# Controlador_de_corriente.net
KiCad netlist of a schematic drawn in Altium Designer
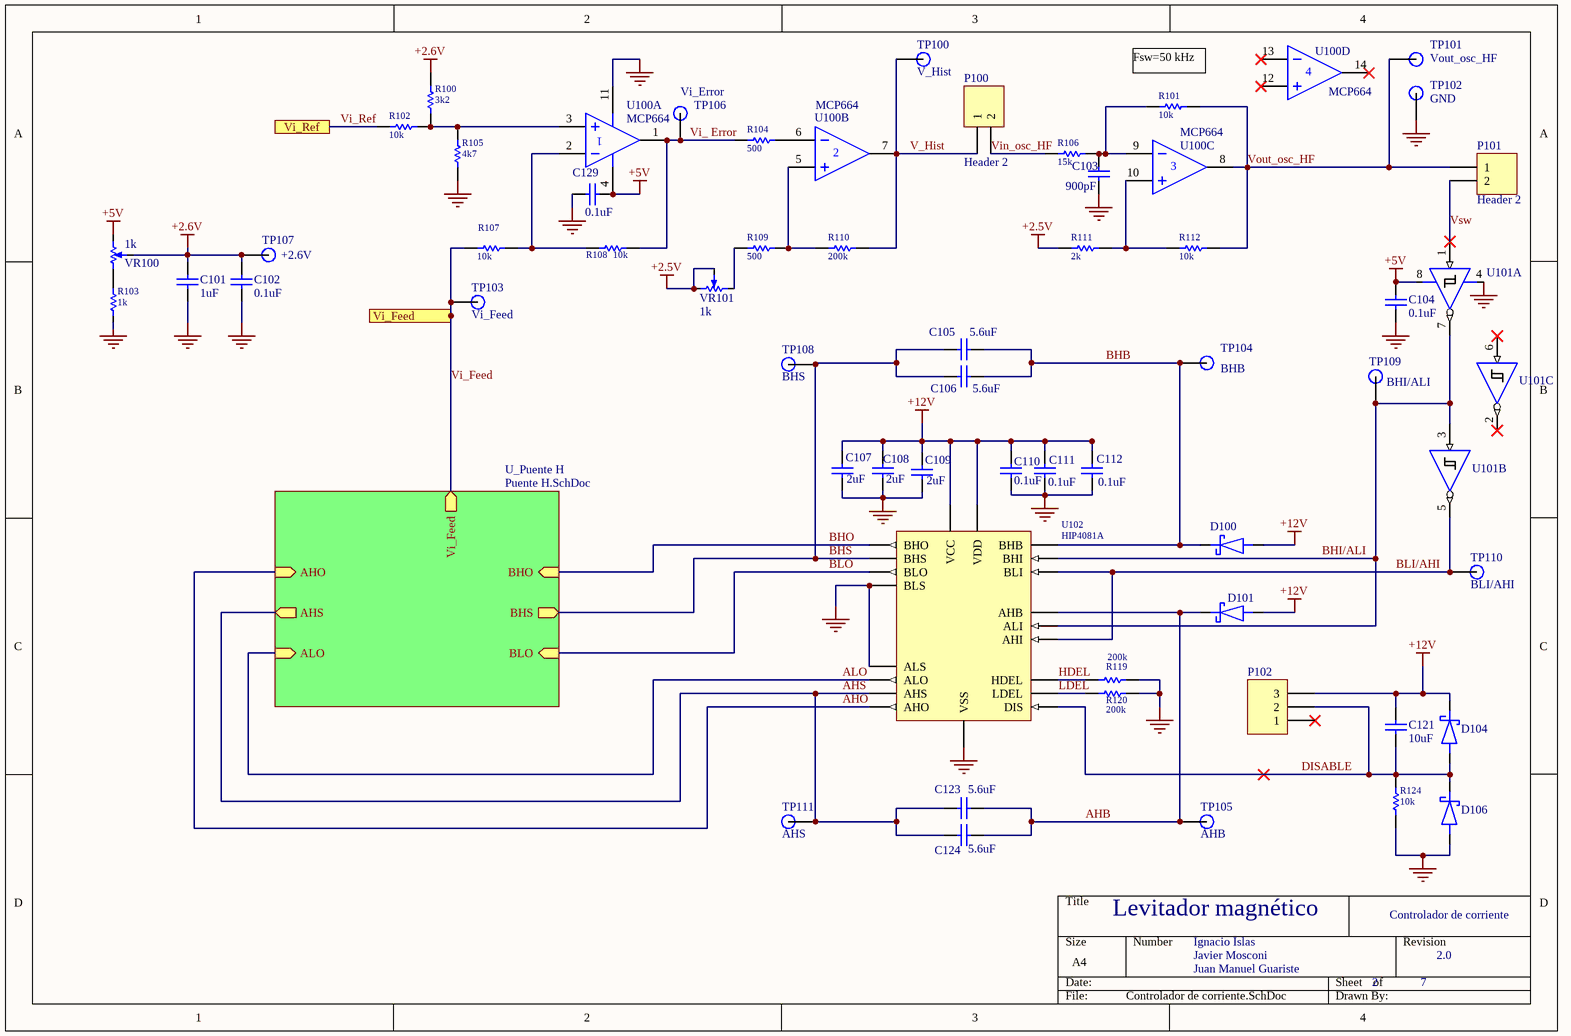
[diagram p0: Controlador de corriente.SchDoc]

(export (version "E")
  (design (tool "Eeschema 10.0.6"))
  (components
    (comp (ref "C101")
      (value "1uF")
      (footprint "C1206")
      (description "CAP CER 1UF 25V X7R 1206")
      (fields (field (name "MANUFACTURER") "CAL-CHIP ELECTRONICS, INC.") (field (name "Comment") "Capacitor"))
      (libsource (lib "Levitador_GMI") (part "Capacitor"))
    )
    (comp (ref "C102")
      (value "0.1uF")
      (footprint "C1206")
      (description "CAP CER 0.1UF 50V X7R 1206")
      (fields (field (name "MANUFACTURER") "Venkel") (field (name "Comment") "Capacitor"))
      (libsource (lib "Levitador_GMI") (part "Capacitor"))
    )
    (comp (ref "C103")
      (value "900pF")
      (footprint "C1206")
      (description "CAP CER 910PF 50V NP0 1206")
      (fields (field (name "MANUFACTURER") "KEMET") (field (name "Comment") "Capacitor"))
      (libsource (lib "Levitador_GMI") (part "Capacitor"))
    )
    (comp (ref "C104")
      (value "0.1uF")
      (footprint "C1206")
      (description "CAP CER 0.1UF 50V X7R 1206")
      (fields (field (name "MANUFACTURER") "Venkel") (field (name "Comment") "Capacitor"))
      (libsource (lib "Levitador_GMI") (part "Capacitor"))
    )
    (comp (ref "C105")
      (value "5.6uF")
      (footprint "C1206")
      (description "CAP CER 4.7UF 50V X7R 1206")
      (fields (field (name "MANUFACTURER") "Samsung Electro-Mechanics") (field (name "Comment") "Capacitor"))
      (libsource (lib "Levitador_GMI") (part "Capacitor"))
    )
    (comp (ref "C106")
      (value "5.6uF")
      (footprint "C1206")
      (description "CAP CER 4.7UF 50V X7R 1206")
      (fields (field (name "MANUFACTURER") "Samsung Electro-Mechanics") (field (name "Comment") "Capacitor"))
      (libsource (lib "Levitador_GMI") (part "Capacitor"))
    )
    (comp (ref "C107")
      (value "2uF")
      (footprint "C1206")
      (description "CAP1206 X5R 2.2UF 20% 35V")
      (fields (field (name "MANUFACTURER") "CAL-CHIP ELECTRONICS, INC.") (field (name "Comment") "Capacitor"))
      (libsource (lib "Levitador_GMI") (part "Capacitor"))
    )
    (comp (ref "C108")
      (value "2uF")
      (footprint "C1206")
      (description "CAP1206 X5R 2.2UF 20% 35V")
      (fields (field (name "MANUFACTURER") "CAL-CHIP ELECTRONICS, INC.") (field (name "Comment") "Capacitor"))
      (libsource (lib "Levitador_GMI") (part "Capacitor"))
    )
    (comp (ref "C109")
      (value "2uF")
      (footprint "C1206")
      (description "CAP1206 X5R 2.2UF 20% 35V")
      (fields (field (name "MANUFACTURER") "CAL-CHIP ELECTRONICS, INC.") (field (name "Comment") "Capacitor"))
      (libsource (lib "Levitador_GMI") (part "Capacitor"))
    )
    (comp (ref "C110")
      (value "0.1uF")
      (footprint "C1206")
      (description "CAP CER 0.1UF 50V X7R 1206")
      (fields (field (name "MANUFACTURER") "Venkel") (field (name "Comment") "Capacitor"))
      (libsource (lib "Levitador_GMI") (part "Capacitor"))
    )
    (comp (ref "C111")
      (value "0.1uF")
      (footprint "C1206")
      (description "CAP CER 0.1UF 50V X7R 1206")
      (fields (field (name "MANUFACTURER") "Venkel") (field (name "Comment") "Capacitor"))
      (libsource (lib "Levitador_GMI") (part "Capacitor"))
    )
    (comp (ref "C112")
      (value "0.1uF")
      (footprint "C1206")
      (description "CAP CER 0.1UF 50V X7R 1206")
      (fields (field (name "MANUFACTURER") "Venkel") (field (name "Comment") "Capacitor"))
      (libsource (lib "Levitador_GMI") (part "Capacitor"))
    )
    (comp (ref "C121")
      (value "10uF")
      (footprint "C1206")
      (description "CAP CER 10UF 16V X7R 1206")
      (fields (field (name "MANUFACTURER") "CAL-CHIP ELECTRONICS, INC.") (field (name "Comment") "Capacitor"))
      (libsource (lib "Levitador_GMI") (part "Capacitor"))
    )
    (comp (ref "C123")
      (value "5.6uF")
      (footprint "C1206")
      (description "CAP CER 4.7UF 50V X7R 1206")
      (fields (field (name "MANUFACTURER") "Samsung Electro-Mechanics") (field (name "Comment") "Capacitor"))
      (libsource (lib "Levitador_GMI") (part "Capacitor"))
    )
    (comp (ref "C124")
      (value "5.6uF")
      (footprint "C1206")
      (description "CAP CER 4.7UF 50V X7R 1206")
      (fields (field (name "MANUFACTURER") "Samsung Electro-Mechanics") (field (name "Comment") "Capacitor"))
      (libsource (lib "Levitador_GMI") (part "Capacitor"))
    )
    (comp (ref "C129")
      (value "0.1uF")
      (footprint "C1206")
      (description "CAP CER 0.1UF 50V X7R 1206")
      (fields (field (name "MANUFACTURER") "Venkel") (field (name "Comment") "Capacitor"))
      (libsource (lib "Levitador_GMI") (part "Capacitor"))
    )
    (comp (ref "D100")
      (value "RSX205LAM30TR")
      (footprint "SODFL4725X105N")
      (description "DIODE SCHOTTKY 30V 2A PMDTM")
      (libsource (lib "Levitador_GMI") (part "RSX205LAM30TR"))
    )
    (comp (ref "D101")
      (value "RSX205LAM30TR")
      (footprint "SODFL4725X105N")
      (description "DIODE SCHOTTKY 30V 2A PMDTM")
      (libsource (lib "Levitador_GMI") (part "RSX205LAM30TR"))
    )
    (comp (ref "D104")
      (value "RSX205LAM30TR")
      (footprint "SODFL4725X105N")
      (description "DIODE SCHOTTKY 30V 2A PMDTM")
      (libsource (lib "Levitador_GMI") (part "RSX205LAM30TR"))
    )
    (comp (ref "D106")
      (value "RSX205LAM30TR")
      (footprint "SODFL4725X105N")
      (description "DIODE SCHOTTKY 30V 2A PMDTM")
      (libsource (lib "Levitador_GMI") (part "RSX205LAM30TR"))
    )
    (comp (ref "P100")
      (value "Header 2")
      (footprint "HDR1X2")
      (description "TERM BLK 2P SIDE ENT 2.54MM PCB")
      (fields (field (name "MANUFACTURER") "TE Connectivity AMP Connectors"))
      (libsource (lib "Levitador_GMI") (part "Header 2"))
    )
    (comp (ref "P101")
      (value "Header 2")
      (footprint "HDR1X2")
      (description "TERM BLK 2P SIDE ENT 2.54MM PCB")
      (fields (field (name "MANUFACTURER") "TE Connectivity AMP Connectors"))
      (libsource (lib "") (part "Header 2_1"))
    )
    (comp (ref "P102")
      (value "Header 3")
      (footprint "HDR1X3")
      (description "TERM BLK 3P SIDE ENT 2.54MM PCB")
      (fields (field (name "MANUFACTURER") "TE Connectivity AMP Connectors"))
      (libsource (lib "Levitador_GMI") (part "Header 3"))
    )
    (comp (ref "R100")
      (value "3k2")
      (footprint "Levitador_GMI:R1206")
      (description "RES 3.2K OHM 1% 1/4W 1206")
      (fields (field (name "MANUFACTURER") "KOA Speer Electronics, Inc.") (field (name "TOLERANCE") "1%"))
      (libsource (lib "Levitador_GMI") (part "R1206"))
    )
    (comp (ref "R101")
      (value "10k")
      (footprint "Levitador_GMI:R1206")
      (description "RES 10K OHM 1% 1/4W 1206")
      (fields (field (name "MANUFACTURER") "YAGEO") (field (name "TOLERANCE") "1%"))
      (libsource (lib "Levitador_GMI") (part "R1206"))
    )
    (comp (ref "R102")
      (value "10k")
      (footprint "Levitador_GMI:R1206")
      (description "RES 10K OHM 1% 1/4W 1206")
      (fields (field (name "MANUFACTURER") "YAGEO") (field (name "TOLERANCE") "1%"))
      (libsource (lib "Levitador_GMI") (part "R1206"))
    )
    (comp (ref "R103")
      (value "1k")
      (footprint "Levitador_GMI:R1206")
      (description "RES 1K OHM 1% 1/4W 1206")
      (fields (field (name "MANUFACTURER") "Stackpole Electronics Inc") (field (name "TOLERANCE") "1%"))
      (libsource (lib "Levitador_GMI") (part "R1206"))
    )
    (comp (ref "R104")
      (value "500")
      (footprint "Levitador_GMI:R1206")
      (description "RES SMD 500 OHM 0.1% 0.3W 1206")
      (fields
        (field (name "MANUFACTURER") "Vishay Foil Resistors (Division of Vishay Precision Group)")
        (field (name "TOLERANCE") "0.1%")
      )
      (libsource (lib "Levitador_GMI") (part "R1206"))
    )
    (comp (ref "R105")
      (value "4k7")
      (footprint "Levitador_GMI:R1206")
      (description "RES 4.7K OHM 1% 1/4W 1206")
      (fields (field (name "MANUFACTURER") "Stackpole Electronics Inc") (field (name "TOLERANCE") "1%"))
      (libsource (lib "Levitador_GMI") (part "R1206"))
    )
    (comp (ref "R106")
      (value "15k")
      (footprint "Levitador_GMI:R1206")
      (description "RES 15K OHM 1% 1/4W 1206")
      (fields (field (name "MANUFACTURER") "Vishay Dale") (field (name "TOLERANCE") "1%"))
      (libsource (lib "Levitador_GMI") (part "R1206"))
    )
    (comp (ref "R107")
      (value "10k")
      (footprint "Levitador_GMI:R1206")
      (description "RES 10K OHM 1% 1/4W 1206")
      (fields (field (name "MANUFACTURER") "YAGEO") (field (name "TOLERANCE") "1%"))
      (libsource (lib "Levitador_GMI") (part "R1206"))
    )
    (comp (ref "R108")
      (value "10k")
      (footprint "Levitador_GMI:R1206")
      (description "RES 10K OHM 1% 1/4W 1206")
      (fields (field (name "MANUFACTURER") "YAGEO") (field (name "TOLERANCE") "1%"))
      (libsource (lib "Levitador_GMI") (part "R1206"))
    )
    (comp (ref "R109")
      (value "500")
      (footprint "Levitador_GMI:R1206")
      (description "RES SMD 500 OHM 0.1% 0.3W 1206")
      (fields
        (field (name "MANUFACTURER") "Vishay Foil Resistors (Division of Vishay Precision Group)")
        (field (name "TOLERANCE") "0.1%")
      )
      (libsource (lib "Levitador_GMI") (part "R1206"))
    )
    (comp (ref "R110")
      (value "200k")
      (footprint "Levitador_GMI:R1206")
      (description "RES 200K OHM 1% 1/4W 1206")
      (fields (field (name "MANUFACTURER") "YAGEO") (field (name "TOLERANCE") "1%"))
      (libsource (lib "Levitador_GMI") (part "R1206"))
    )
    (comp (ref "R111")
      (value "2k")
      (footprint "Levitador_GMI:R1206")
      (description "RES 2K OHM 1% 1/4W 1206")
      (fields (field (name "MANUFACTURER") "Stackpole Electronics Inc") (field (name "TOLERANCE") "1%"))
      (libsource (lib "Levitador_GMI") (part "R1206"))
    )
    (comp (ref "R112")
      (value "10k")
      (footprint "Levitador_GMI:R1206")
      (description "RES 10K OHM 1% 1/4W 1206")
      (fields (field (name "MANUFACTURER") "YAGEO") (field (name "TOLERANCE") "1%"))
      (libsource (lib "Levitador_GMI") (part "R1206"))
    )
    (comp (ref "R119")
      (value "200k")
      (footprint "Levitador_GMI:R1206")
      (description "RES 200K OHM 1% 1/4W 1206")
      (fields (field (name "MANUFACTURER") "YAGEO") (field (name "TOLERANCE") "1%"))
      (libsource (lib "Levitador_GMI") (part "R1206"))
    )
    (comp (ref "R120")
      (value "200k")
      (footprint "Levitador_GMI:R1206")
      (description "RES 200K OHM 1% 1/4W 1206")
      (fields (field (name "MANUFACTURER") "YAGEO") (field (name "TOLERANCE") "1%"))
      (libsource (lib "Levitador_GMI") (part "R1206"))
    )
    (comp (ref "R124")
      (value "10k")
      (footprint "Levitador_GMI:R1206")
      (description "RES 10K OHM 1% 1/4W 1206")
      (fields (field (name "MANUFACTURER") "YAGEO") (field (name "TOLERANCE") "1%"))
      (libsource (lib "Levitador_GMI") (part "R1206"))
    )
    (comp (ref "TP100")
      (value "V_Hist")
      (footprint "TestPoint Keystone 5000 Silver-Red")
      (description "PC TEST POINT MINIATURE RED")
      (fields (field (name "MANUFACTURER") "Keystone Electronics"))
      (libsource (lib "Levitador_GMI") (part "Testpoint"))
    )
    (comp (ref "TP101")
      (value "Vout_osc_HF")
      (footprint "TestPoint Keystone 5000 Silver-Red")
      (description "PC TEST POINT MINIATURE RED")
      (fields (field (name "MANUFACTURER") "Keystone Electronics"))
      (libsource (lib "Levitador_GMI") (part "Testpoint"))
    )
    (comp (ref "TP102")
      (value "GND")
      (footprint "TestPoint Keystone 5000 Silver-Red")
      (description "PC TEST POINT MINIATURE RED")
      (fields (field (name "MANUFACTURER") "Keystone Electronics"))
      (libsource (lib "Levitador_GMI") (part "Testpoint"))
    )
    (comp (ref "TP103")
      (value "Vi_Feed")
      (footprint "TestPoint Keystone 5000 Silver-Red")
      (description "PC TEST POINT MINIATURE RED")
      (fields (field (name "MANUFACTURER") "Keystone Electronics"))
      (libsource (lib "Levitador_GMI") (part "Testpoint"))
    )
    (comp (ref "TP104")
      (value "BHB")
      (footprint "TestPoint Keystone 5000 Silver-Red")
      (description "PC TEST POINT MINIATURE RED")
      (fields (field (name "MANUFACTURER") "Keystone Electronics"))
      (libsource (lib "Levitador_GMI") (part "Testpoint"))
    )
    (comp (ref "TP105")
      (value "AHB")
      (footprint "TestPoint Keystone 5000 Silver-Red")
      (description "PC TEST POINT MINIATURE RED")
      (fields (field (name "MANUFACTURER") "Keystone Electronics"))
      (libsource (lib "Levitador_GMI") (part "Testpoint"))
    )
    (comp (ref "TP106")
      (value "Vi_Error")
      (footprint "TestPoint Keystone 5000 Silver-Red")
      (description "PC TEST POINT MINIATURE RED")
      (fields (field (name "MANUFACTURER") "Keystone Electronics"))
      (libsource (lib "Levitador_GMI") (part "Testpoint"))
    )
    (comp (ref "TP107")
      (value "+2.6V")
      (footprint "TestPoint Keystone 5000 Silver-Red")
      (description "PC TEST POINT MINIATURE RED")
      (fields (field (name "MANUFACTURER") "Keystone Electronics"))
      (libsource (lib "Levitador_GMI") (part "Testpoint"))
    )
    (comp (ref "TP108")
      (value "BHS")
      (footprint "TestPoint Keystone 5000 Silver-Red")
      (description "PC TEST POINT MINIATURE RED")
      (fields (field (name "MANUFACTURER") "Keystone Electronics"))
      (libsource (lib "Levitador_GMI") (part "Testpoint"))
    )
    (comp (ref "TP109")
      (value "BHI/ALI")
      (footprint "TestPoint Keystone 5000 Silver-Red")
      (description "PC TEST POINT MINIATURE RED")
      (fields (field (name "MANUFACTURER") "Keystone Electronics"))
      (libsource (lib "Levitador_GMI") (part "Testpoint"))
    )
    (comp (ref "TP110")
      (value "BLI/AHI")
      (footprint "TestPoint Keystone 5000 Silver-Red")
      (description "PC TEST POINT MINIATURE RED")
      (fields (field (name "MANUFACTURER") "Keystone Electronics"))
      (libsource (lib "Levitador_GMI") (part "Testpoint"))
    )
    (comp (ref "TP111")
      (value "AHS")
      (footprint "TestPoint Keystone 5000 Silver-Red")
      (description "PC TEST POINT MINIATURE RED")
      (fields (field (name "MANUFACTURER") "Keystone Electronics"))
      (libsource (lib "Levitador_GMI") (part "Testpoint"))
    )
    (comp (ref "U100")
      (value "MCP664")
      (footprint "SOIC14")
      (description "IC OPAMP GP 4 CIRCUIT 14TSSOP")
      (fields (field (name "MANUFACTURER") "Microchip Technology"))
      (libsource (lib "Levitador_GMI") (part "MCP664"))
    )
    (comp (ref "U101")
      (value "SN74LVC3G06DCUT")
      (footprint "SOP50P310X90-8N")
      (description "IC INVERTER OD 3CH 3-INP 8VSSOP")
      (fields (field (name "MANUFACTURER") "Texas Instruments"))
      (libsource (lib "Levitador_GMI") (part "SN74LVC3G06DCUT"))
    )
    (comp (ref "U102")
      (value "HIP4081A")
      (footprint "SOIC20")
      (description "IC GATE DRVR HALF-BRIDGE 20SOIC")
      (fields (field (name "MANUFACTURER") "Renesas Electronics America Inc"))
      (libsource (lib "Levitador_GMI") (part "HIP4081A"))
    )
    (comp (ref "VR100")
      (value "1k")
      (footprint "3299Y1203LF")
      (description "e")
      (fields (field (name "MANUFACTURER") "Bourns Inc.") (field (name "Comment") "Trimmer (Thru-Hole)"))
      (libsource (lib "Levitador_GMI") (part "Trimmer"))
    )
    (comp (ref "VR101")
      (value "1k")
      (footprint "3299Y1203LF")
      (description "TRIMMER 1K OHM 0.5W PC PIN TOP")
      (fields (field (name "MANUFACTURER") "Bourns Inc.") (field (name "Comment") "Trimmer (Thru-Hole)"))
      (libsource (lib "Levitador_GMI") (part "Trimmer"))
    )
  )
  (nets
    (net (code "1") (name "+2.5V") (class "Default")
      (node (ref "R111") (pin "2") (pinfunction "2_2") (pintype "passive"))
      (node (ref "VR101") (pin "1") (pinfunction "CCW_1") (pintype "passive"))
      (node (ref "VR101") (pin "2") (pinfunction "W_2") (pintype "passive"))
    )
    (net (code "2") (name "+2.6V") (class "Default")
      (node (ref "C101") (pin "2") (pinfunction "2_2") (pintype "passive"))
      (node (ref "C102") (pin "2") (pinfunction "2_2") (pintype "passive"))
      (node (ref "R100") (pin "2") (pinfunction "2_2") (pintype "passive"))
      (node (ref "TP107") (pin "1") (pinfunction "1_1") (pintype "passive"))
      (node (ref "VR100") (pin "2") (pinfunction "W_2") (pintype "passive"))
    )
    (net (code "3") (name "+5V") (class "Default")
      (node (ref "C104") (pin "2") (pinfunction "2_2") (pintype "passive"))
      (node (ref "C129") (pin "2") (pinfunction "2_2") (pintype "passive"))
      (node (ref "U100") (pin "4") (pinfunction "V+_4") (pintype "power_in"))
      (node (ref "U101") (pin "8") (pinfunction "Vcc_8") (pintype "power_in"))
      (node (ref "VR100") (pin "1") (pinfunction "CCW_1") (pintype "passive"))
    )
    (net (code "4") (name "+12V") (class "Default")
      (node (ref "C107") (pin "2") (pinfunction "2_2") (pintype "passive"))
      (node (ref "C108") (pin "2") (pinfunction "2_2") (pintype "passive"))
      (node (ref "C109") (pin "2") (pinfunction "2_2") (pintype "passive"))
      (node (ref "C110") (pin "2") (pinfunction "2_2") (pintype "passive"))
      (node (ref "C111") (pin "2") (pinfunction "2_2") (pintype "passive"))
      (node (ref "C112") (pin "2") (pinfunction "2_2") (pintype "passive"))
      (node (ref "C121") (pin "2") (pinfunction "2_2") (pintype "passive"))
      (node (ref "D100") (pin "2") (pinfunction "A_2") (pintype "passive"))
      (node (ref "D101") (pin "2") (pinfunction "A_2") (pintype "passive"))
      (node (ref "D104") (pin "1") (pinfunction "K_1") (pintype "passive"))
      (node (ref "P102") (pin "3") (pinfunction "3_3") (pintype "passive"))
      (node (ref "U102") (pin "15") (pinfunction "VCC_15") (pintype "power_in"))
      (node (ref "U102") (pin "16") (pinfunction "VDD_16") (pintype "power_in"))
    )
    (net (code "5") (name "/AHB") (class "Default")
      (node (ref "C123") (pin "2") (pinfunction "2_2") (pintype "passive"))
      (node (ref "C124") (pin "2") (pinfunction "2_2") (pintype "passive"))
      (node (ref "D101") (pin "1") (pinfunction "K_1") (pintype "passive"))
      (node (ref "TP105") (pin "1") (pinfunction "1_1") (pintype "passive"))
      (node (ref "U102") (pin "10") (pinfunction "AHB_10") (pintype "power_in"))
    )
    (net (code "6") (name "/AHO") (class "Default")
      (node (ref "U102") (pin "11") (pinfunction "AHO_11") (pintype "output"))
    )
    (net (code "7") (name "/AHS") (class "Default")
      (node (ref "C123") (pin "1") (pinfunction "1_1") (pintype "passive"))
      (node (ref "C124") (pin "1") (pinfunction "1_1") (pintype "passive"))
      (node (ref "TP111") (pin "1") (pinfunction "1_1") (pintype "passive"))
      (node (ref "U102") (pin "12") (pinfunction "AHS_12") (pintype "passive"))
    )
    (net (code "8") (name "/ALO") (class "Default")
      (node (ref "U102") (pin "13") (pinfunction "ALO_13") (pintype "output"))
    )
    (net (code "9") (name "/BHB") (class "Default")
      (node (ref "C105") (pin "2") (pinfunction "2_2") (pintype "passive"))
      (node (ref "C106") (pin "2") (pinfunction "2_2") (pintype "passive"))
      (node (ref "D100") (pin "1") (pinfunction "K_1") (pintype "passive"))
      (node (ref "TP104") (pin "1") (pinfunction "1_1") (pintype "passive"))
      (node (ref "U102") (pin "1") (pinfunction "BHB_1") (pintype "power_in"))
    )
    (net (code "10") (name "/BHI{slash}ALI") (class "Default")
      (node (ref "TP109") (pin "1") (pinfunction "1_1") (pintype "passive"))
      (node (ref "U101") (pin "3") (pinfunction "2A_3") (pintype "input"))
      (node (ref "U101") (pin "7") (pinfunction "1Y_7") (pintype "output"))
      (node (ref "U102") (pin "2") (pinfunction "BHI_2") (pintype "input"))
      (node (ref "U102") (pin "6") (pinfunction "ALI_6") (pintype "input"))
    )
    (net (code "11") (name "/BHO") (class "Default")
      (node (ref "U102") (pin "20") (pinfunction "BHO_20") (pintype "output"))
    )
    (net (code "12") (name "/BHS") (class "Default")
      (node (ref "C105") (pin "1") (pinfunction "1_1") (pintype "passive"))
      (node (ref "C106") (pin "1") (pinfunction "1_1") (pintype "passive"))
      (node (ref "TP108") (pin "1") (pinfunction "1_1") (pintype "passive"))
      (node (ref "U102") (pin "19") (pinfunction "BHS_19") (pintype "passive"))
    )
    (net (code "13") (name "/BLI{slash}AHI") (class "Default")
      (node (ref "TP110") (pin "1") (pinfunction "1_1") (pintype "passive"))
      (node (ref "U101") (pin "5") (pinfunction "2Y_5") (pintype "output"))
      (node (ref "U102") (pin "5") (pinfunction "BLI_5") (pintype "input"))
      (node (ref "U102") (pin "7") (pinfunction "AHI_7") (pintype "input"))
    )
    (net (code "14") (name "/BLO") (class "Default")
      (node (ref "U102") (pin "18") (pinfunction "BLO_18") (pintype "output"))
    )
    (net (code "15") (name "/DISABLE") (class "Default")
      (node (ref "C121") (pin "1") (pinfunction "1_1") (pintype "passive"))
      (node (ref "D104") (pin "2") (pinfunction "A_2") (pintype "passive"))
      (node (ref "D106") (pin "1") (pinfunction "K_1") (pintype "passive"))
      (node (ref "P102") (pin "2") (pinfunction "2_2") (pintype "passive"))
      (node (ref "R124") (pin "2") (pinfunction "2_2") (pintype "passive"))
      (node (ref "U102") (pin "3") (pinfunction "DIS_3") (pintype "input"))
    )
    (net (code "16") (name "/HDEL") (class "Default")
      (node (ref "R119") (pin "1") (pinfunction "1_1") (pintype "passive"))
      (node (ref "U102") (pin "8") (pinfunction "HDEL_8") (pintype "passive"))
    )
    (net (code "17") (name "/LDEL") (class "Default")
      (node (ref "R120") (pin "1") (pinfunction "1_1") (pintype "passive"))
      (node (ref "U102") (pin "9") (pinfunction "LDEL_9") (pintype "passive"))
    )
    (net (code "18") (name "/V_Hist") (class "Default")
      (node (ref "P100") (pin "1") (pinfunction "1_1") (pintype "passive"))
      (node (ref "R110") (pin "2") (pinfunction "2_2") (pintype "passive"))
      (node (ref "TP100") (pin "1") (pinfunction "1_1") (pintype "passive"))
      (node (ref "U100") (pin "7") (pinfunction "OUT_7") (pintype "passive"))
    )
    (net (code "19") (name "/Vi_ Error") (class "Default")
      (node (ref "R104") (pin "1") (pinfunction "1_1") (pintype "passive"))
      (node (ref "R108") (pin "2") (pinfunction "2_2") (pintype "passive"))
      (node (ref "TP106") (pin "1") (pinfunction "1_1") (pintype "passive"))
      (node (ref "U100") (pin "1") (pinfunction "OUT_1") (pintype "passive"))
    )
    (net (code "20") (name "/Vi_Feed") (class "Default")
      (node (ref "R107") (pin "1") (pinfunction "1_1") (pintype "passive"))
      (node (ref "TP103") (pin "1") (pinfunction "1_1") (pintype "passive"))
    )
    (net (code "21") (name "/Vi_Ref") (class "Default")
      (node (ref "R102") (pin "1") (pinfunction "1_1") (pintype "passive"))
    )
    (net (code "22") (name "/Vin_osc_HF") (class "Default")
      (node (ref "P100") (pin "2") (pinfunction "2_2") (pintype "passive"))
      (node (ref "R106") (pin "1") (pinfunction "1_1") (pintype "passive"))
    )
    (net (code "23") (name "/Vout_osc_HF") (class "Default")
      (node (ref "P101") (pin "1") (pinfunction "1_1") (pintype "passive"))
      (node (ref "R101") (pin "2") (pinfunction "2_2") (pintype "passive"))
      (node (ref "R112") (pin "2") (pinfunction "2_2") (pintype "passive"))
      (node (ref "TP101") (pin "1") (pinfunction "1_1") (pintype "passive"))
      (node (ref "U100") (pin "8") (pinfunction "OUT_8") (pintype "passive"))
    )
    (net (code "24") (name "/Vsw") (class "Default")
      (node (ref "P101") (pin "2") (pinfunction "2_2") (pintype "passive"))
      (node (ref "U101") (pin "1") (pinfunction "1A_1") (pintype "input"))
    )
    (net (code "25") (name "GND") (class "Default")
      (node (ref "C101") (pin "1") (pinfunction "1_1") (pintype "passive"))
      (node (ref "C102") (pin "1") (pinfunction "1_1") (pintype "passive"))
      (node (ref "C103") (pin "2") (pinfunction "2_2") (pintype "passive"))
      (node (ref "C104") (pin "1") (pinfunction "1_1") (pintype "passive"))
      (node (ref "C107") (pin "1") (pinfunction "1_1") (pintype "passive"))
      (node (ref "C108") (pin "1") (pinfunction "1_1") (pintype "passive"))
      (node (ref "C109") (pin "1") (pinfunction "1_1") (pintype "passive"))
      (node (ref "C110") (pin "1") (pinfunction "1_1") (pintype "passive"))
      (node (ref "C111") (pin "1") (pinfunction "1_1") (pintype "passive"))
      (node (ref "C112") (pin "1") (pinfunction "1_1") (pintype "passive"))
      (node (ref "C129") (pin "1") (pinfunction "1_1") (pintype "passive"))
      (node (ref "D106") (pin "2") (pinfunction "A_2") (pintype "passive"))
      (node (ref "R103") (pin "1") (pinfunction "1_1") (pintype "passive"))
      (node (ref "R105") (pin "1") (pinfunction "1_1") (pintype "passive"))
      (node (ref "R119") (pin "2") (pinfunction "2_2") (pintype "passive"))
      (node (ref "R120") (pin "2") (pinfunction "2_2") (pintype "passive"))
      (node (ref "R124") (pin "1") (pinfunction "1_1") (pintype "passive"))
      (node (ref "TP102") (pin "1") (pinfunction "1_1") (pintype "passive"))
      (node (ref "U100") (pin "11") (pinfunction "V-_11") (pintype "power_in"))
      (node (ref "U101") (pin "4") (pinfunction "GND_4") (pintype "power_in"))
      (node (ref "U102") (pin "14") (pinfunction "ALS_14") (pintype "passive"))
      (node (ref "U102") (pin "17") (pinfunction "BLS_17") (pintype "passive"))
      (node (ref "U102") (pin "4") (pinfunction "VSS_4") (pintype "power_in"))
    )
    (net (code "26") (name "Net-(U100A-IN+)") (class "Default")
      (node (ref "R100") (pin "1") (pinfunction "1_1") (pintype "passive"))
      (node (ref "R102") (pin "2") (pinfunction "2_2") (pintype "passive"))
      (node (ref "R105") (pin "2") (pinfunction "2_2") (pintype "passive"))
      (node (ref "U100") (pin "3") (pinfunction "IN+_3") (pintype "passive"))
    )
    (net (code "27") (name "Net-(U100A-IN-)") (class "Default")
      (node (ref "R107") (pin "2") (pinfunction "2_2") (pintype "passive"))
      (node (ref "R108") (pin "1") (pinfunction "1_1") (pintype "passive"))
      (node (ref "U100") (pin "2") (pinfunction "IN-_2") (pintype "passive"))
    )
    (net (code "28") (name "Net-(U100B-IN+)") (class "Default")
      (node (ref "R109") (pin "1") (pinfunction "1_1") (pintype "passive"))
      (node (ref "R110") (pin "1") (pinfunction "1_1") (pintype "passive"))
      (node (ref "U100") (pin "5") (pinfunction "IN+_5") (pintype "passive"))
    )
    (net (code "29") (name "Net-(U100B-IN-)") (class "Default")
      (node (ref "R104") (pin "2") (pinfunction "2_2") (pintype "passive"))
      (node (ref "U100") (pin "6") (pinfunction "IN-_6") (pintype "passive"))
    )
    (net (code "30") (name "Net-(U100C-IN+)") (class "Default")
      (node (ref "R111") (pin "1") (pinfunction "1_1") (pintype "passive"))
      (node (ref "R112") (pin "1") (pinfunction "1_1") (pintype "passive"))
      (node (ref "U100") (pin "10") (pinfunction "IN+_10") (pintype "passive"))
    )
    (net (code "31") (name "Net-(U100C-IN-)") (class "Default")
      (node (ref "C103") (pin "1") (pinfunction "1_1") (pintype "passive"))
      (node (ref "R101") (pin "1") (pinfunction "1_1") (pintype "passive"))
      (node (ref "R106") (pin "2") (pinfunction "2_2") (pintype "passive"))
      (node (ref "U100") (pin "9") (pinfunction "IN-_9") (pintype "passive"))
    )
    (net (code "32") (name "Net-(VR100-CW)") (class "Default")
      (node (ref "R103") (pin "2") (pinfunction "2_2") (pintype "passive"))
      (node (ref "VR100") (pin "3") (pinfunction "CW_3") (pintype "passive"))
    )
    (net (code "33") (name "Net-(VR101-CW)") (class "Default")
      (node (ref "R109") (pin "2") (pinfunction "2_2") (pintype "passive"))
      (node (ref "VR101") (pin "3") (pinfunction "CW_3") (pintype "passive"))
    )
    (net (code "34") (name "unconnected-(P102-Pad1)") (class "Default")
      (node (ref "P102") (pin "1") (pinfunction "1_1") (pintype "passive+no_connect"))
    )
    (net (code "35") (name "unconnected-(U100D-IN+-Pad12)") (class "Default")
      (node (ref "U100") (pin "12") (pinfunction "IN+_12") (pintype "passive+no_connect"))
    )
    (net (code "36") (name "unconnected-(U100D-IN--Pad13)") (class "Default")
      (node (ref "U100") (pin "13") (pinfunction "IN-_13") (pintype "passive+no_connect"))
    )
    (net (code "37") (name "unconnected-(U100D-OUT-Pad14)") (class "Default")
      (node (ref "U100") (pin "14") (pinfunction "OUT_14") (pintype "passive+no_connect"))
    )
    (net (code "38") (name "unconnected-(U101C-3A-Pad6)") (class "Default")
      (node (ref "U101") (pin "6") (pinfunction "3A_6") (pintype "input+no_connect"))
    )
    (net (code "39") (name "unconnected-(U101C-3Y-Pad2)") (class "Default")
      (node (ref "U101") (pin "2") (pinfunction "3Y_2") (pintype "output+no_connect"))
    )
  )
)
